# doodle_with_clock6.net
KiCad netlist of a schematic drawn in EAGLE
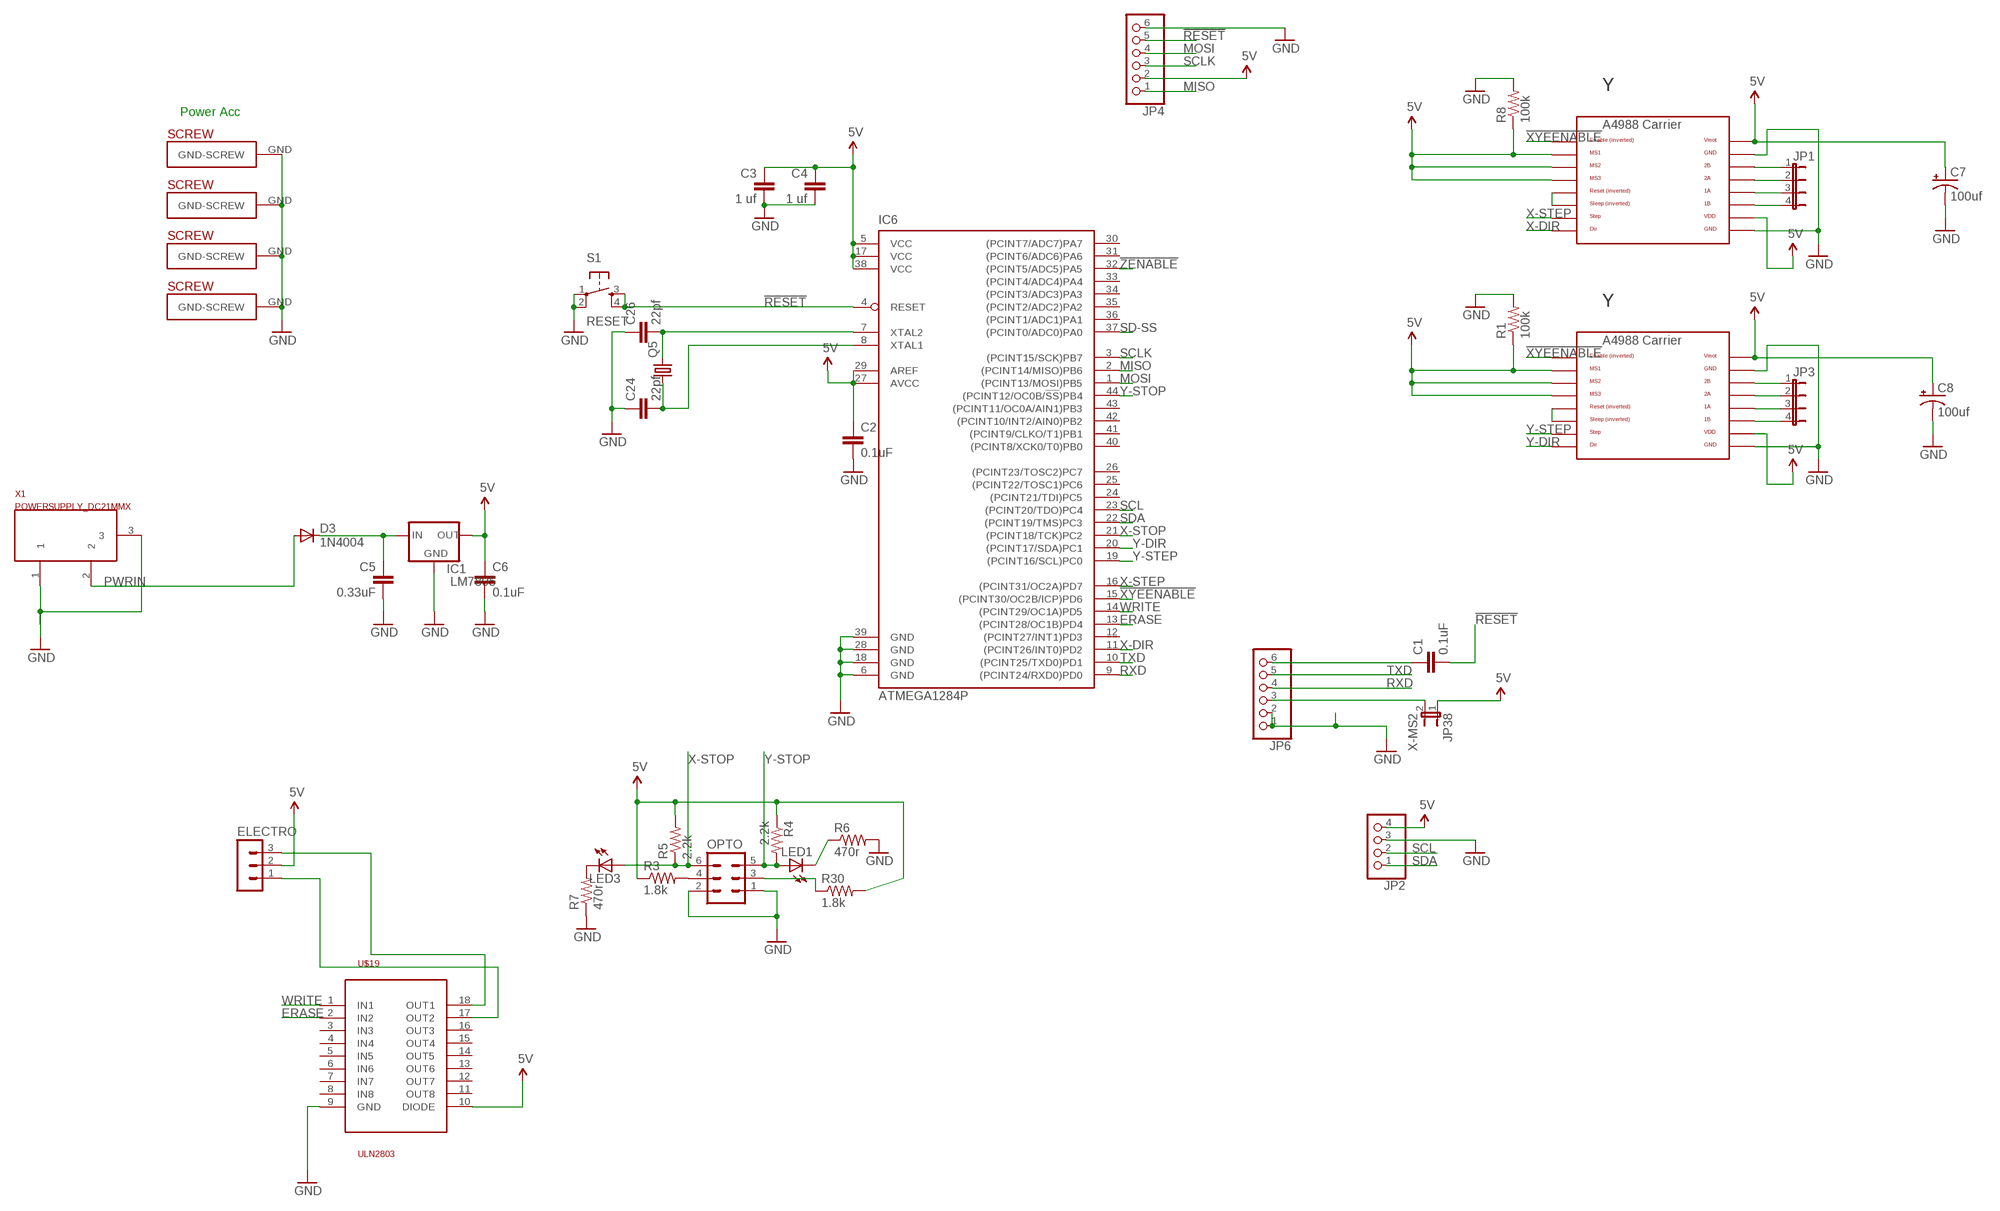
[diagram p0: schematic, sheet 1]

(export (version "E")
  (design (tool "Eeschema 10.0.6"))
  (components
    (comp (ref "C1")
      (value "0.1uF")
      (footprint "eagle-import:CAP-PTH-SMALL2")
      (libsource (lib "eagle-import") (part "CAPPTH2"))
    )
    (comp (ref "C2")
      (value "0.1uF")
      (footprint "eagle-import:CAP-PTH-SMALL2")
      (libsource (lib "eagle-import") (part "CAPPTH2"))
    )
    (comp (ref "C3")
      (value "1 uf")
      (footprint "eagle-import:CAP-PTH-SMALL2")
      (libsource (lib "eagle-import") (part "CAPPTH2"))
    )
    (comp (ref "C4")
      (value "1 uf")
      (footprint "eagle-import:CAP-PTH-SMALL2")
      (libsource (lib "eagle-import") (part "CAPPTH2"))
    )
    (comp (ref "C5")
      (value "0.33uF")
      (footprint "eagle-import:CAP-PTH-SMALL2")
      (libsource (lib "eagle-import") (part "CAPPTH2"))
    )
    (comp (ref "C6")
      (value "0.1uF")
      (footprint "eagle-import:CAP-PTH-SMALL2")
      (libsource (lib "eagle-import") (part "CAPPTH2"))
    )
    (comp (ref "C7")
      (value "100uf")
      (footprint "eagle-import:CPOL-RADIAL-100UF-25V")
      (libsource (lib "eagle-import") (part "CAP_POLPTH1"))
    )
    (comp (ref "C8")
      (value "100uf")
      (footprint "eagle-import:CPOL-RADIAL-100UF-25V")
      (libsource (lib "eagle-import") (part "CAP_POLPTH1"))
    )
    (comp (ref "C24")
      (value "22pf")
      (footprint "eagle-import:CAP-PTH-SMALL2")
      (libsource (lib "eagle-import") (part "CAPPTH2"))
    )
    (comp (ref "C26")
      (value "22pf")
      (footprint "eagle-import:CAP-PTH-SMALL2")
      (libsource (lib "eagle-import") (part "CAPPTH2"))
    )
    (comp (ref "D3")
      (value "1N4004")
      (footprint "eagle-import:DO41-10")
      (libsource (lib "eagle-import") (part "1N4004"))
    )
    (comp (ref "ELECTRO")
      (value "MA03-1")
      (footprint "eagle-import:MA03-1")
      (libsource (lib "eagle-import") (part "MA03-1"))
    )
    (comp (ref "IC1")
      (value "LM7805")
      (footprint "eagle-import:78XXL-CUSTOM")
      (libsource (lib "eagle-import") (part "V_REG_78XX"))
    )
    (comp (ref "IC6")
      (value "ATMEGA1284P")
      (footprint "eagle-import:TQFP44")
      (fields (field (name "MPN") "ATMEGA644PV-10AU"))
      (libsource (lib "eagle-import") (part "ATMEGA644A"))
    )
    (comp (ref "JP1")
      (value "JP4E")
      (footprint "eagle-import:JP4")
      (libsource (lib "eagle-import") (part "JP4E"))
    )
    (comp (ref "JP2")
      (value "PINHD-1X4")
      (footprint "eagle-import:1X04")
      (libsource (lib "eagle-import") (part "PINHD-1X4"))
    )
    (comp (ref "JP3")
      (value "JP4E")
      (footprint "eagle-import:JP4")
      (libsource (lib "eagle-import") (part "JP4E"))
    )
    (comp (ref "JP4")
      (value "PINHD-1X6/90")
      (footprint "eagle-import:1X06_90")
      (libsource (lib "eagle-import") (part "PINHD-1X6/90"))
    )
    (comp (ref "JP6")
      (value "PINHD-1X6")
      (footprint "eagle-import:1X06")
      (libsource (lib "eagle-import") (part "PINHD-1X6"))
    )
    (comp (ref "JP38")
      (value "X-MS2")
      (footprint "eagle-import:1X02")
      (libsource (lib "eagle-import") (part "JUMPER-2PTH"))
    )
    (comp (ref "LED1")
      (value "LED3MM")
      (footprint "eagle-import:LED3MM")
      (libsource (lib "eagle-import") (part "LED3MM"))
    )
    (comp (ref "LED3")
      (value "LED3MM")
      (footprint "eagle-import:LED3MM")
      (libsource (lib "eagle-import") (part "LED3MM"))
    )
    (comp (ref "OPTO")
      (value "MA03-2")
      (footprint "eagle-import:MA03-2")
      (libsource (lib "eagle-import") (part "MA03-2"))
    )
    (comp (ref "Q5")
      (value "CRYSTALHC49S")
      (footprint "eagle-import:HC49_S")
      (libsource (lib "eagle-import") (part "CRYSTALHC49S"))
    )
    (comp (ref "R1")
      (value "100k")
      (footprint "eagle-import:0207_7")
      (libsource (lib "eagle-import") (part "R-US_0207/7"))
    )
    (comp (ref "R3")
      (value "1.8k")
      (footprint "eagle-import:0207_2V")
      (libsource (lib "eagle-import") (part "resistor_R-US_0207/2V"))
    )
    (comp (ref "R4")
      (value "2.2k")
      (footprint "eagle-import:0207_2V")
      (libsource (lib "eagle-import") (part "resistor_R-US_0207/2V"))
    )
    (comp (ref "R5")
      (value "2.2k")
      (footprint "eagle-import:0207_2V")
      (libsource (lib "eagle-import") (part "resistor_R-US_0207/2V"))
    )
    (comp (ref "R6")
      (value "470r")
      (footprint "eagle-import:0207_2V")
      (libsource (lib "eagle-import") (part "resistor_R-US_0207/2V"))
    )
    (comp (ref "R7")
      (value "470r")
      (footprint "eagle-import:0207_2V")
      (libsource (lib "eagle-import") (part "resistor_R-US_0207/2V"))
    )
    (comp (ref "R8")
      (value "100k")
      (footprint "eagle-import:0207_7")
      (libsource (lib "eagle-import") (part "R-US_0207/7"))
    )
    (comp (ref "R30")
      (value "1.8k")
      (footprint "eagle-import:0207_2V")
      (libsource (lib "eagle-import") (part "resistor_R-US_0207/2V"))
    )
    (comp (ref "S1")
      (value "RESET")
      (footprint "eagle-import:TACTILE-PTH")
      (libsource (lib "eagle-import") (part "TAC_SWITCHPTH"))
    )
    (comp (ref "U$1")
      (value "A4988BREAKOUT")
      (footprint "eagle-import:A4988BREAKOUT")
      (libsource (lib "eagle-import") (part "A4988BREAKOUT"))
    )
    (comp (ref "U$7")
      (value "A4988BREAKOUT")
      (footprint "eagle-import:A4988BREAKOUT")
      (libsource (lib "eagle-import") (part "A4988BREAKOUT"))
    )
    (comp (ref "U$14")
      (value "PLATED-SCREW")
      (footprint "eagle-import:PLATEDSCREW")
      (libsource (lib "eagle-import") (part "PLATED-SCREW"))
    )
    (comp (ref "U$17")
      (value "PLATED-SCREW")
      (footprint "eagle-import:PLATEDSCREW")
      (libsource (lib "eagle-import") (part "PLATED-SCREW"))
    )
    (comp (ref "U$18")
      (value "PLATED-SCREW")
      (footprint "eagle-import:PLATEDSCREW")
      (libsource (lib "eagle-import") (part "PLATED-SCREW"))
    )
    (comp (ref "U$19")
      (value "ULN2803")
      (footprint "eagle-import:SO18L")
      (libsource (lib "eagle-import") (part "ULN2803"))
    )
    (comp (ref "U$38")
      (value "PLATED-SCREW")
      (footprint "eagle-import:PLATEDSCREW")
      (libsource (lib "eagle-import") (part "PLATED-SCREW"))
    )
    (comp (ref "X1")
      (value "POWERSUPPLY_DC21MMX")
      (footprint "eagle-import:POWERSUPPLY_DC-21MM")
      (libsource (lib "eagle-import") (part "POWERSUPPLY_DC21MMX"))
    )
  )
  (nets
    (net (code "1") (name "/ERASE") (class "Default")
      (node (ref "IC6") (pin "13") (pinfunction "(PCINT28/OC1B)PD4_13") (pintype "bidirectional"))
      (node (ref "U$19") (pin "2") (pinfunction "IN2_2") (pintype "input"))
    )
    (net (code "2") (name "/MISO") (class "Default")
      (node (ref "IC6") (pin "2") (pinfunction "(PCINT14/MISO)PB6_2") (pintype "bidirectional"))
      (node (ref "JP4") (pin "1") (pinfunction "1_1") (pintype "passive"))
    )
    (net (code "3") (name "/MOSI") (class "Default")
      (node (ref "IC6") (pin "1") (pinfunction "(PCINT13/MOSI)PB5_1") (pintype "bidirectional"))
      (node (ref "JP4") (pin "4") (pinfunction "4_4") (pintype "passive"))
    )
    (net (code "4") (name "/PWRIN") (class "Default")
      (node (ref "D3") (pin "A") (pinfunction "A_A") (pintype "passive"))
      (node (ref "X1") (pin "2") (pinfunction "2_2") (pintype "power_in"))
    )
    (net (code "5") (name "/RXD") (class "Default")
      (node (ref "IC6") (pin "9") (pinfunction "(PCINT24/RXD0)PD0_9") (pintype "bidirectional"))
      (node (ref "JP6") (pin "4") (pinfunction "4_4") (pintype "passive"))
    )
    (net (code "6") (name "/SCL") (class "Default")
      (node (ref "IC6") (pin "23") (pinfunction "(PCINT20/TDO)PC4_23") (pintype "output"))
      (node (ref "JP2") (pin "2") (pinfunction "2_2") (pintype "passive"))
    )
    (net (code "7") (name "/SCLK") (class "Default")
      (node (ref "IC6") (pin "3") (pinfunction "(PCINT15/SCK)PB7_3") (pintype "bidirectional"))
      (node (ref "JP4") (pin "3") (pinfunction "3_3") (pintype "passive"))
    )
    (net (code "8") (name "/SD-SS") (class "Default")
      (node (ref "IC6") (pin "37") (pinfunction "(PCINT0/ADC0)PA0_37") (pintype "bidirectional"))
    )
    (net (code "9") (name "/SDA") (class "Default")
      (node (ref "IC6") (pin "22") (pinfunction "(PCINT19/TMS)PC3_22") (pintype "output"))
      (node (ref "JP2") (pin "1") (pinfunction "1_1") (pintype "passive"))
    )
    (net (code "10") (name "/TXD") (class "Default")
      (node (ref "IC6") (pin "10") (pinfunction "(PCINT25/TXD0)PD1_10") (pintype "bidirectional"))
      (node (ref "JP6") (pin "5") (pinfunction "5_5") (pintype "passive"))
    )
    (net (code "11") (name "/WRITE") (class "Default")
      (node (ref "IC6") (pin "14") (pinfunction "(PCINT29/OC1A)PD5_14") (pintype "bidirectional"))
      (node (ref "U$19") (pin "1") (pinfunction "IN1_1") (pintype "input"))
    )
    (net (code "12") (name "/X-DIR") (class "Default")
      (node (ref "IC6") (pin "11") (pinfunction "(PCINT26/INT0)PD2_11") (pintype "bidirectional"))
      (node (ref "U$7") (pin "DIR") (pinfunction "DIR_DIR") (pintype "input"))
    )
    (net (code "13") (name "/X-STEP") (class "Default")
      (node (ref "IC6") (pin "16") (pinfunction "(PCINT31/OC2A)PD7_16") (pintype "bidirectional"))
      (node (ref "U$7") (pin "STEP") (pinfunction "STEP_STEP") (pintype "input"))
    )
    (net (code "14") (name "/X-STOP") (class "Default")
      (node (ref "IC6") (pin "21") (pinfunction "(PCINT18/TCK)PC2_21") (pintype "output"))
      (node (ref "LED3") (pin "A") (pinfunction "A_A") (pintype "passive"))
      (node (ref "OPTO") (pin "6") (pinfunction "6_6") (pintype "passive"))
      (node (ref "R5") (pin "1") (pinfunction "1_1") (pintype "passive"))
    )
    (net (code "15") (name "/Y-DIR") (class "Default")
      (node (ref "IC6") (pin "20") (pinfunction "(PCINT17/SDA)PC1_20") (pintype "output"))
      (node (ref "U$1") (pin "DIR") (pinfunction "DIR_DIR") (pintype "input"))
    )
    (net (code "16") (name "/Y-STEP") (class "Default")
      (node (ref "IC6") (pin "19") (pinfunction "(PCINT16/SCL)PC0_19") (pintype "output"))
      (node (ref "U$1") (pin "STEP") (pinfunction "STEP_STEP") (pintype "input"))
    )
    (net (code "17") (name "/Y-STOP") (class "Default")
      (node (ref "IC6") (pin "44") (pinfunction "(PCINT12/OC0B/~{SS})PB4_44") (pintype "bidirectional"))
      (node (ref "LED1") (pin "A") (pinfunction "A_A") (pintype "passive"))
      (node (ref "OPTO") (pin "5") (pinfunction "5_5") (pintype "passive"))
      (node (ref "R4") (pin "2") (pinfunction "2_2") (pintype "passive"))
    )
    (net (code "18") (name "/~{RESET}") (class "Default")
      (node (ref "C1") (pin "2") (pinfunction "2_2") (pintype "passive"))
      (node (ref "IC6") (pin "4") (pinfunction "RESET_4") (pintype "input"))
      (node (ref "JP4") (pin "5") (pinfunction "5_5") (pintype "passive"))
      (node (ref "S1") (pin "3") (pinfunction "3_3") (pintype "passive"))
      (node (ref "S1") (pin "4") (pinfunction "4_4") (pintype "passive"))
    )
    (net (code "19") (name "/~{XYEENABLE}") (class "Default")
      (node (ref "IC6") (pin "15") (pinfunction "(PCINT30/OC2B/ICP)PD6_15") (pintype "bidirectional"))
      (node (ref "U$1") (pin "EN") (pinfunction "EN_EN") (pintype "input"))
      (node (ref "U$7") (pin "EN") (pinfunction "EN_EN") (pintype "input"))
    )
    (net (code "20") (name "/~{ZENABLE}") (class "Default")
      (node (ref "IC6") (pin "32") (pinfunction "(PCINT5/ADC5)PA5_32") (pintype "bidirectional"))
    )
    (net (code "21") (name "5V") (class "Default")
      (node (ref "C2") (pin "1") (pinfunction "1_1") (pintype "passive"))
      (node (ref "C3") (pin "1") (pinfunction "1_1") (pintype "passive"))
      (node (ref "C4") (pin "1") (pinfunction "1_1") (pintype "passive"))
      (node (ref "C6") (pin "1") (pinfunction "1_1") (pintype "passive"))
      (node (ref "C7") (pin "1") (pinfunction "+_1") (pintype "passive"))
      (node (ref "C8") (pin "1") (pinfunction "+_1") (pintype "passive"))
      (node (ref "ELECTRO") (pin "2") (pinfunction "2_2") (pintype "passive"))
      (node (ref "IC1") (pin "OUT") (pinfunction "OUT_OUT") (pintype "output"))
      (node (ref "IC6") (pin "17") (pinfunction "VCC_17") (pintype "power_in"))
      (node (ref "IC6") (pin "27") (pinfunction "AVCC_27") (pintype "power_in"))
      (node (ref "IC6") (pin "29") (pinfunction "AREF_29") (pintype "passive"))
      (node (ref "IC6") (pin "38") (pinfunction "VCC_38") (pintype "power_in"))
      (node (ref "IC6") (pin "5") (pinfunction "VCC_5") (pintype "power_in"))
      (node (ref "JP2") (pin "4") (pinfunction "4_4") (pintype "passive"))
      (node (ref "JP38") (pin "1") (pinfunction "1_1") (pintype "passive"))
      (node (ref "JP4") (pin "2") (pinfunction "2_2") (pintype "passive"))
      (node (ref "R1") (pin "1") (pinfunction "1_1") (pintype "passive"))
      (node (ref "R3") (pin "1") (pinfunction "1_1") (pintype "passive"))
      (node (ref "R30") (pin "2") (pinfunction "2_2") (pintype "passive"))
      (node (ref "R4") (pin "1") (pinfunction "1_1") (pintype "passive"))
      (node (ref "R5") (pin "2") (pinfunction "2_2") (pintype "passive"))
      (node (ref "R8") (pin "1") (pinfunction "1_1") (pintype "passive"))
      (node (ref "U$1") (pin "MS1") (pinfunction "MS1_MS1") (pintype "input"))
      (node (ref "U$1") (pin "MS2") (pinfunction "MS2_MS2") (pintype "input"))
      (node (ref "U$1") (pin "MS3") (pinfunction "MS3_MS3") (pintype "input"))
      (node (ref "U$1") (pin "VDD") (pinfunction "VDD_VDD") (pintype "power_in"))
      (node (ref "U$1") (pin "VMOT") (pinfunction "VMOT_VMOT") (pintype "power_in"))
      (node (ref "U$19") (pin "10") (pinfunction "DIODE_10") (pintype "power_in"))
      (node (ref "U$7") (pin "MS1") (pinfunction "MS1_MS1") (pintype "input"))
      (node (ref "U$7") (pin "MS2") (pinfunction "MS2_MS2") (pintype "input"))
      (node (ref "U$7") (pin "MS3") (pinfunction "MS3_MS3") (pintype "input"))
      (node (ref "U$7") (pin "VDD") (pinfunction "VDD_VDD") (pintype "power_in"))
      (node (ref "U$7") (pin "VMOT") (pinfunction "VMOT_VMOT") (pintype "power_in"))
    )
    (net (code "22") (name "GND") (class "Default")
      (node (ref "C2") (pin "2") (pinfunction "2_2") (pintype "passive"))
      (node (ref "C24") (pin "1") (pinfunction "1_1") (pintype "passive"))
      (node (ref "C26") (pin "1") (pinfunction "1_1") (pintype "passive"))
      (node (ref "C3") (pin "2") (pinfunction "2_2") (pintype "passive"))
      (node (ref "C4") (pin "2") (pinfunction "2_2") (pintype "passive"))
      (node (ref "C5") (pin "2") (pinfunction "2_2") (pintype "passive"))
      (node (ref "C6") (pin "2") (pinfunction "2_2") (pintype "passive"))
      (node (ref "C7") (pin "2") (pinfunction "-_2") (pintype "passive"))
      (node (ref "C8") (pin "2") (pinfunction "-_2") (pintype "passive"))
      (node (ref "IC1") (pin "GND") (pinfunction "GND_GND") (pintype "input"))
      (node (ref "IC6") (pin "18") (pinfunction "GND_18") (pintype "power_in"))
      (node (ref "IC6") (pin "28") (pinfunction "GND_28") (pintype "power_in"))
      (node (ref "IC6") (pin "39") (pinfunction "GND_39") (pintype "power_in"))
      (node (ref "IC6") (pin "6") (pinfunction "GND_6") (pintype "power_in"))
      (node (ref "JP2") (pin "3") (pinfunction "3_3") (pintype "passive"))
      (node (ref "JP4") (pin "6") (pinfunction "6_6") (pintype "passive"))
      (node (ref "JP6") (pin "1") (pinfunction "1_1") (pintype "passive"))
      (node (ref "JP6") (pin "2") (pinfunction "2_2") (pintype "passive"))
      (node (ref "OPTO") (pin "1") (pinfunction "1_1") (pintype "passive"))
      (node (ref "OPTO") (pin "2") (pinfunction "2_2") (pintype "passive"))
      (node (ref "R1") (pin "2") (pinfunction "2_2") (pintype "passive"))
      (node (ref "R6") (pin "2") (pinfunction "2_2") (pintype "passive"))
      (node (ref "R7") (pin "1") (pinfunction "1_1") (pintype "passive"))
      (node (ref "R8") (pin "2") (pinfunction "2_2") (pintype "passive"))
      (node (ref "S1") (pin "1") (pinfunction "1_1") (pintype "passive"))
      (node (ref "S1") (pin "2") (pinfunction "2_2") (pintype "passive"))
      (node (ref "U$1") (pin "GND") (pinfunction "GND_GND") (pintype "power_in"))
      (node (ref "U$1") (pin "GND@0") (pinfunction "GND_GND@0") (pintype "power_in"))
      (node (ref "U$14") (pin "GND") (pinfunction "GND-SCREW_GND") (pintype "bidirectional"))
      (node (ref "U$17") (pin "GND") (pinfunction "GND-SCREW_GND") (pintype "bidirectional"))
      (node (ref "U$18") (pin "GND") (pinfunction "GND-SCREW_GND") (pintype "bidirectional"))
      (node (ref "U$19") (pin "9") (pinfunction "GND_9") (pintype "power_in"))
      (node (ref "U$38") (pin "GND") (pinfunction "GND-SCREW_GND") (pintype "bidirectional"))
      (node (ref "U$7") (pin "GND") (pinfunction "GND_GND") (pintype "power_in"))
      (node (ref "U$7") (pin "GND@0") (pinfunction "GND_GND@0") (pintype "power_in"))
      (node (ref "X1") (pin "1") (pinfunction "1_1") (pintype "power_in"))
      (node (ref "X1") (pin "3") (pinfunction "3_3") (pintype "power_in"))
    )
    (net (code "23") (name "Net-(C1-Pad1)") (class "Default")
      (node (ref "C1") (pin "1") (pinfunction "1_1") (pintype "passive"))
      (node (ref "JP6") (pin "6") (pinfunction "6_6") (pintype "passive"))
    )
    (net (code "24") (name "Net-(C5-Pad1)") (class "Default")
      (node (ref "C5") (pin "1") (pinfunction "1_1") (pintype "passive"))
      (node (ref "D3") (pin "C") (pinfunction "C_C") (pintype "passive"))
      (node (ref "IC1") (pin "IN") (pinfunction "IN_IN") (pintype "input"))
    )
    (net (code "25") (name "Net-(IC6-XTAL1)") (class "Default")
      (node (ref "C24") (pin "2") (pinfunction "2_2") (pintype "passive"))
      (node (ref "IC6") (pin "8") (pinfunction "XTAL1_8") (pintype "bidirectional"))
      (node (ref "Q5") (pin "1") (pinfunction "1_1") (pintype "passive"))
    )
    (net (code "26") (name "Net-(IC6-XTAL2)") (class "Default")
      (node (ref "C26") (pin "2") (pinfunction "2_2") (pintype "passive"))
      (node (ref "IC6") (pin "7") (pinfunction "XTAL2_7") (pintype "bidirectional"))
      (node (ref "Q5") (pin "2") (pinfunction "2_2") (pintype "passive"))
    )
    (net (code "27") (name "Net-(JP1-Pad1)") (class "Default")
      (node (ref "JP1") (pin "1") (pinfunction "1_1") (pintype "passive"))
      (node (ref "U$7") (pin "2B") (pinfunction "2B_2B") (pintype "output"))
    )
    (net (code "28") (name "Net-(JP1-Pad2)") (class "Default")
      (node (ref "JP1") (pin "2") (pinfunction "2_2") (pintype "passive"))
      (node (ref "U$7") (pin "2A") (pinfunction "2A_2A") (pintype "output"))
    )
    (net (code "29") (name "Net-(JP1-Pad3)") (class "Default")
      (node (ref "JP1") (pin "3") (pinfunction "3_3") (pintype "passive"))
      (node (ref "U$7") (pin "1A") (pinfunction "1A_1A") (pintype "output"))
    )
    (net (code "30") (name "Net-(JP1-Pad4)") (class "Default")
      (node (ref "JP1") (pin "4") (pinfunction "4_4") (pintype "passive"))
      (node (ref "U$7") (pin "1B") (pinfunction "1B_1B") (pintype "output"))
    )
    (net (code "31") (name "Net-(JP3-Pad1)") (class "Default")
      (node (ref "JP3") (pin "1") (pinfunction "1_1") (pintype "passive"))
      (node (ref "U$1") (pin "2B") (pinfunction "2B_2B") (pintype "output"))
    )
    (net (code "32") (name "Net-(JP3-Pad2)") (class "Default")
      (node (ref "JP3") (pin "2") (pinfunction "2_2") (pintype "passive"))
      (node (ref "U$1") (pin "2A") (pinfunction "2A_2A") (pintype "output"))
    )
    (net (code "33") (name "Net-(JP3-Pad3)") (class "Default")
      (node (ref "JP3") (pin "3") (pinfunction "3_3") (pintype "passive"))
      (node (ref "U$1") (pin "1A") (pinfunction "1A_1A") (pintype "output"))
    )
    (net (code "34") (name "Net-(JP3-Pad4)") (class "Default")
      (node (ref "JP3") (pin "4") (pinfunction "4_4") (pintype "passive"))
      (node (ref "U$1") (pin "1B") (pinfunction "1B_1B") (pintype "output"))
    )
    (net (code "35") (name "Net-(JP38-Pad2)") (class "Default")
      (node (ref "JP38") (pin "2") (pinfunction "2_2") (pintype "passive"))
      (node (ref "JP6") (pin "3") (pinfunction "3_3") (pintype "passive"))
    )
    (net (code "36") (name "Net-(LED1-C)") (class "Default")
      (node (ref "LED1") (pin "K") (pinfunction "C_K") (pintype "passive"))
      (node (ref "R6") (pin "1") (pinfunction "1_1") (pintype "passive"))
    )
    (net (code "37") (name "Net-(LED3-C)") (class "Default")
      (node (ref "LED3") (pin "K") (pinfunction "C_K") (pintype "passive"))
      (node (ref "R7") (pin "2") (pinfunction "2_2") (pintype "passive"))
    )
    (net (code "38") (name "Net-(OPTO-Pad3)") (class "Default")
      (node (ref "OPTO") (pin "3") (pinfunction "3_3") (pintype "passive"))
      (node (ref "R30") (pin "1") (pinfunction "1_1") (pintype "passive"))
    )
    (net (code "39") (name "Net-(OPTO-Pad4)") (class "Default")
      (node (ref "OPTO") (pin "4") (pinfunction "4_4") (pintype "passive"))
      (node (ref "R3") (pin "2") (pinfunction "2_2") (pintype "passive"))
    )
    (net (code "40") (name "Net-(U$1-SLEEP)") (class "Default")
      (node (ref "U$1") (pin "RST") (pinfunction "RST_RST") (pintype "input"))
      (node (ref "U$1") (pin "SLP") (pinfunction "SLEEP_SLP") (pintype "input"))
    )
    (net (code "41") (name "Net-(U$7-SLEEP)") (class "Default")
      (node (ref "U$7") (pin "RST") (pinfunction "RST_RST") (pintype "input"))
      (node (ref "U$7") (pin "SLP") (pinfunction "SLEEP_SLP") (pintype "input"))
    )
    (net (code "42") (name "Net-(U$19-OUT1)") (class "Default")
      (node (ref "ELECTRO") (pin "3") (pinfunction "3_3") (pintype "passive"))
      (node (ref "U$19") (pin "18") (pinfunction "OUT1_18") (pintype "open_collector"))
    )
    (net (code "43") (name "Net-(U$19-OUT2)") (class "Default")
      (node (ref "ELECTRO") (pin "1") (pinfunction "1_1") (pintype "passive"))
      (node (ref "U$19") (pin "17") (pinfunction "OUT2_17") (pintype "open_collector"))
    )
    (net (code "44") (name "unconnected-(IC6-(PCINT1{slash}ADC1)PA1-Pad36)") (class "Default")
      (node (ref "IC6") (pin "36") (pinfunction "(PCINT1/ADC1)PA1_36") (pintype "bidirectional"))
    )
    (net (code "45") (name "unconnected-(IC6-(PCINT2{slash}ADC2)PA2-Pad35)") (class "Default")
      (node (ref "IC6") (pin "35") (pinfunction "(PCINT2/ADC2)PA2_35") (pintype "bidirectional"))
    )
    (net (code "46") (name "unconnected-(IC6-(PCINT3{slash}ADC3)PA3-Pad34)") (class "Default")
      (node (ref "IC6") (pin "34") (pinfunction "(PCINT3/ADC3)PA3_34") (pintype "bidirectional"))
    )
    (net (code "47") (name "unconnected-(IC6-(PCINT4{slash}ADC4)PA4-Pad33)") (class "Default")
      (node (ref "IC6") (pin "33") (pinfunction "(PCINT4/ADC4)PA4_33") (pintype "bidirectional"))
    )
    (net (code "48") (name "unconnected-(IC6-(PCINT6{slash}ADC6)PA6-Pad31)") (class "Default")
      (node (ref "IC6") (pin "31") (pinfunction "(PCINT6/ADC6)PA6_31") (pintype "bidirectional"))
    )
    (net (code "49") (name "unconnected-(IC6-(PCINT7{slash}ADC7)PA7-Pad30)") (class "Default")
      (node (ref "IC6") (pin "30") (pinfunction "(PCINT7/ADC7)PA7_30") (pintype "bidirectional"))
    )
    (net (code "50") (name "unconnected-(IC6-(PCINT8{slash}XCK0{slash}T0)PB0-Pad40)") (class "Default")
      (node (ref "IC6") (pin "40") (pinfunction "(PCINT8/XCK0/T0)PB0_40") (pintype "bidirectional"))
    )
    (net (code "51") (name "unconnected-(IC6-(PCINT9{slash}CLKO{slash}T1)PB1-Pad41)") (class "Default")
      (node (ref "IC6") (pin "41") (pinfunction "(PCINT9/CLKO/T1)PB1_41") (pintype "bidirectional"))
    )
    (net (code "52") (name "unconnected-(IC6-(PCINT10{slash}INT2{slash}AIN0)PB2-Pad42)") (class "Default")
      (node (ref "IC6") (pin "42") (pinfunction "(PCINT10/INT2/AIN0)PB2_42") (pintype "bidirectional"))
    )
    (net (code "53") (name "unconnected-(IC6-(PCINT11{slash}OC0A{slash}AIN1)PB3-Pad43)") (class "Default")
      (node (ref "IC6") (pin "43") (pinfunction "(PCINT11/OC0A/AIN1)PB3_43") (pintype "bidirectional"))
    )
    (net (code "54") (name "unconnected-(IC6-(PCINT21{slash}TDI)PC5-Pad24)") (class "Default")
      (node (ref "IC6") (pin "24") (pinfunction "(PCINT21/TDI)PC5_24") (pintype "output"))
    )
    (net (code "55") (name "unconnected-(IC6-(PCINT22{slash}TOSC1)PC6-Pad25)") (class "Default")
      (node (ref "IC6") (pin "25") (pinfunction "(PCINT22/TOSC1)PC6_25") (pintype "output"))
    )
    (net (code "56") (name "unconnected-(IC6-(PCINT23{slash}TOSC2)PC7-Pad26)") (class "Default")
      (node (ref "IC6") (pin "26") (pinfunction "(PCINT23/TOSC2)PC7_26") (pintype "output"))
    )
    (net (code "57") (name "unconnected-(IC6-(PCINT27{slash}INT1)PD3-Pad12)") (class "Default")
      (node (ref "IC6") (pin "12") (pinfunction "(PCINT27/INT1)PD3_12") (pintype "bidirectional"))
    )
    (net (code "58") (name "unconnected-(U$19-IN3-Pad3)") (class "Default")
      (node (ref "U$19") (pin "3") (pinfunction "IN3_3") (pintype "input"))
    )
    (net (code "59") (name "unconnected-(U$19-IN4-Pad4)") (class "Default")
      (node (ref "U$19") (pin "4") (pinfunction "IN4_4") (pintype "input"))
    )
    (net (code "60") (name "unconnected-(U$19-IN5-Pad5)") (class "Default")
      (node (ref "U$19") (pin "5") (pinfunction "IN5_5") (pintype "input"))
    )
    (net (code "61") (name "unconnected-(U$19-IN6-Pad6)") (class "Default")
      (node (ref "U$19") (pin "6") (pinfunction "IN6_6") (pintype "input"))
    )
    (net (code "62") (name "unconnected-(U$19-IN7-Pad7)") (class "Default")
      (node (ref "U$19") (pin "7") (pinfunction "IN7_7") (pintype "input"))
    )
    (net (code "63") (name "unconnected-(U$19-IN8-Pad8)") (class "Default")
      (node (ref "U$19") (pin "8") (pinfunction "IN8_8") (pintype "input"))
    )
    (net (code "64") (name "unconnected-(U$19-OUT3-Pad16)") (class "Default")
      (node (ref "U$19") (pin "16") (pinfunction "OUT3_16") (pintype "open_collector"))
    )
    (net (code "65") (name "unconnected-(U$19-OUT4-Pad15)") (class "Default")
      (node (ref "U$19") (pin "15") (pinfunction "OUT4_15") (pintype "open_collector"))
    )
    (net (code "66") (name "unconnected-(U$19-OUT5-Pad14)") (class "Default")
      (node (ref "U$19") (pin "14") (pinfunction "OUT5_14") (pintype "open_collector"))
    )
    (net (code "67") (name "unconnected-(U$19-OUT6-Pad13)") (class "Default")
      (node (ref "U$19") (pin "13") (pinfunction "OUT6_13") (pintype "open_collector"))
    )
    (net (code "68") (name "unconnected-(U$19-OUT7-Pad12)") (class "Default")
      (node (ref "U$19") (pin "12") (pinfunction "OUT7_12") (pintype "open_collector"))
    )
    (net (code "69") (name "unconnected-(U$19-OUT8-Pad11)") (class "Default")
      (node (ref "U$19") (pin "11") (pinfunction "OUT8_11") (pintype "open_collector"))
    )
  )
)
